# SparkFun_Cypress_USBUART_BOB.net
KiCad netlist of a schematic drawn in EAGLE
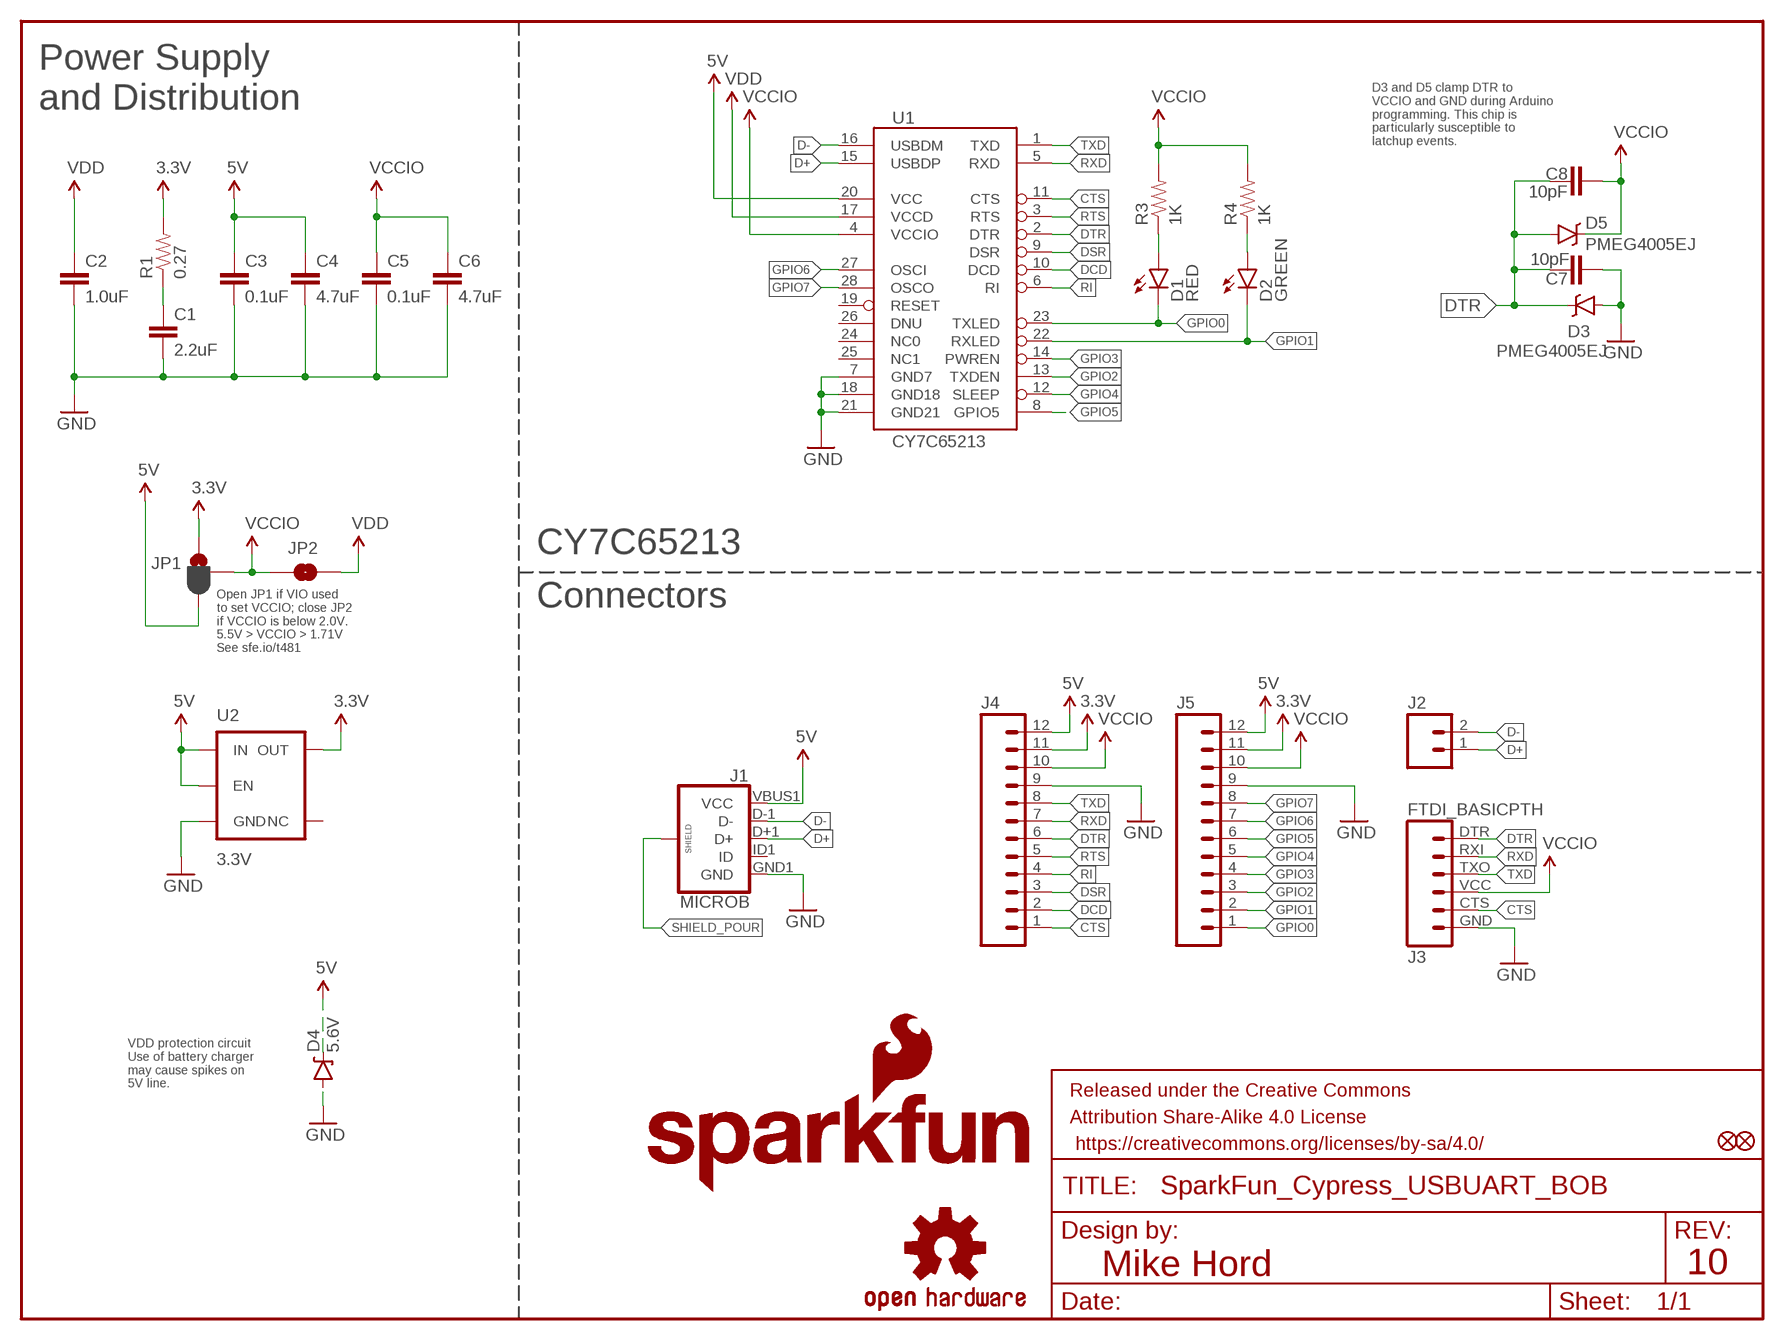
[diagram p0: schematic, sheet 1]

(export (version "E")
  (design (tool "Eeschema 10.0.6"))
  (components
    (comp (ref "C1")
      (value "2.2uF")
      (footprint "eagle-import:0603-CAP")
      (libsource (lib "eagle-import") (part "2.2UF-10V-20%(0603)"))
    )
    (comp (ref "C2")
      (value "1.0uF")
      (footprint "eagle-import:0603-CAP")
      (libsource (lib "eagle-import") (part "1.0UF-16V-10%(0603)"))
    )
    (comp (ref "C3")
      (value "0.1uF")
      (footprint "eagle-import:0603-CAP")
      (libsource (lib "eagle-import") (part "0.1UF-25V-5%(0603)"))
    )
    (comp (ref "C4")
      (value "4.7uF")
      (footprint "eagle-import:1206-CAP")
      (libsource (lib "eagle-import") (part "4.7UF-16V-20%,+80%-(1206)"))
    )
    (comp (ref "C5")
      (value "0.1uF")
      (footprint "eagle-import:0603-CAP")
      (libsource (lib "eagle-import") (part "0.1UF-25V-5%(0603)"))
    )
    (comp (ref "C6")
      (value "4.7uF")
      (footprint "eagle-import:1206-CAP")
      (libsource (lib "eagle-import") (part "4.7UF-16V-20%,+80%-(1206)"))
    )
    (comp (ref "C7")
      (value "10pF")
      (footprint "eagle-import:0603-CAP")
      (libsource (lib "eagle-import") (part "10PF-50V-5%(0603)"))
    )
    (comp (ref "C8")
      (value "10pF")
      (footprint "eagle-import:0603-CAP")
      (libsource (lib "eagle-import") (part "10PF-50V-5%(0603)"))
    )
    (comp (ref "D1")
      (value "RED")
      (footprint "eagle-import:LED-0603")
      (libsource (lib "eagle-import") (part "LED-RED0603"))
    )
    (comp (ref "D2")
      (value "GREEN")
      (footprint "eagle-import:LED-0603")
      (libsource (lib "eagle-import") (part "LED-GREEN0603"))
    )
    (comp (ref "D3")
      (value "PMEG4005EJ")
      (footprint "eagle-import:SOD-323")
      (libsource (lib "eagle-import") (part "DIODE-SCHOTTKY-PMEG4005EJ"))
    )
    (comp (ref "D4")
      (value "5.6V")
      (footprint "eagle-import:SOD-323")
      (libsource (lib "eagle-import") (part "DIODE-ZENER5.6V"))
    )
    (comp (ref "D5")
      (value "PMEG4005EJ")
      (footprint "eagle-import:SOD-323")
      (libsource (lib "eagle-import") (part "DIODE-SCHOTTKY-PMEG4005EJ"))
    )
    (comp (ref "FD1")
      (value "FIDUCIALUFIDUCIAL")
      (footprint "eagle-import:MICRO-FIDUCIAL")
      (libsource (lib "eagle-import") (part "FIDUCIALUFIDUCIAL"))
    )
    (comp (ref "FD2")
      (value "FIDUCIALUFIDUCIAL")
      (footprint "eagle-import:MICRO-FIDUCIAL")
      (libsource (lib "eagle-import") (part "FIDUCIALUFIDUCIAL"))
    )
    (comp (ref "FRAME1")
      (value "FRAME-LETTER")
      (footprint "eagle-import:CREATIVE_COMMONS")
      (libsource (lib "eagle-import") (part "FRAME-LETTER"))
    )
    (comp (ref "J1")
      (value "MICROB")
      (footprint "eagle-import:USB-B-MICRO-SMD_V03")
      (libsource (lib "eagle-import") (part "USB_MICROB_PLUGCONN-11752"))
    )
    (comp (ref "J2")
      (value "M02PTH")
      (footprint "eagle-import:1X02")
      (libsource (lib "eagle-import") (part "M02PTH"))
    )
    (comp (ref "J3")
      (value "FTDI_BASICPTH")
      (footprint "eagle-import:FTDI_BASIC")
      (libsource (lib "eagle-import") (part "FTDI_BASICPTH"))
    )
    (comp (ref "J4")
      (value "M12PTH")
      (footprint "eagle-import:1X12")
      (libsource (lib "eagle-import") (part "M12PTH"))
    )
    (comp (ref "J5")
      (value "M12PTH")
      (footprint "eagle-import:1X12")
      (libsource (lib "eagle-import") (part "M12PTH"))
    )
    (comp (ref "JP1")
      (value "JUMPER-PAD-3-2OF3_NC_BY_PASTE")
      (footprint "eagle-import:PAD-JUMPER-3-2OF3_NC_BY_PASTE_YES_SILK_FULL_BOX")
      (libsource (lib "eagle-import") (part "JUMPER-PAD-3-2OF3_NC_BY_PASTE"))
    )
    (comp (ref "JP2")
      (value "JUMPER-PAD-2-NOYES_SILK")
      (footprint "eagle-import:PAD-JUMPER-2-NO_YES_SILK")
      (libsource (lib "eagle-import") (part "JUMPER-PAD-2-NOYES_SILK"))
    )
    (comp (ref "LOGO1")
      (value "SFE_LOGO_NAME_FLAME.1_INCH")
      (footprint "eagle-import:SFE_LOGO_NAME_FLAME_.1")
      (libsource (lib "eagle-import") (part "SFE_LOGO_NAME_FLAME.1_INCH"))
    )
    (comp (ref "LOGO2")
      (value "OSHW-LOGOS")
      (footprint "eagle-import:OSHW-LOGO-S")
      (libsource (lib "eagle-import") (part "OSHW-LOGOS"))
    )
    (comp (ref "R1")
      (value "0.27")
      (footprint "eagle-import:0603-RES")
      (libsource (lib "eagle-import") (part "0.27OHM-1/10W-1%(0603)"))
    )
    (comp (ref "R3")
      (value "1K")
      (footprint "eagle-import:0603-RES")
      (libsource (lib "eagle-import") (part "1KOHM-1/10W-1%(0603)"))
    )
    (comp (ref "R4")
      (value "1K")
      (footprint "eagle-import:0603-RES")
      (libsource (lib "eagle-import") (part "1KOHM-1/10W-1%(0603)"))
    )
    (comp (ref "U1")
      (value "CY7C65213")
      (footprint "eagle-import:SSOP28DB")
      (libsource (lib "eagle-import") (part "CY7C65213"))
    )
    (comp (ref "U2")
      (value "3.3V")
      (footprint "eagle-import:SOT23-5")
      (libsource (lib "eagle-import") (part "V_REG_AP2112K-3.3V"))
    )
  )
  (nets
    (net (code "1") (name "/NC1") (class "Default")
      (node (ref "U1") (pin "25") (pinfunction "NC1_25") (pintype "power_in"))
    )
    (net (code "2") (name "3.3V") (class "Default")
      (node (ref "J4") (pin "11") (pinfunction "11_11") (pintype "passive"))
      (node (ref "J5") (pin "11") (pinfunction "11_11") (pintype "passive"))
      (node (ref "JP1") (pin "1") (pinfunction "1_1") (pintype "passive"))
      (node (ref "R1") (pin "2") (pinfunction "2_2") (pintype "passive"))
      (node (ref "U2") (pin "5") (pinfunction "OUT_5") (pintype "passive"))
    )
    (net (code "3") (name "5V") (class "Default")
      (node (ref "C3") (pin "1") (pinfunction "1_1") (pintype "passive"))
      (node (ref "C4") (pin "1") (pinfunction "1_1") (pintype "passive"))
      (node (ref "D4") (pin "C") (pinfunction "C_C") (pintype "passive"))
      (node (ref "J1") (pin "VBUS1") (pinfunction "VCC_VBUS1") (pintype "bidirectional"))
      (node (ref "J4") (pin "12") (pinfunction "12_12") (pintype "passive"))
      (node (ref "J5") (pin "12") (pinfunction "12_12") (pintype "passive"))
      (node (ref "JP1") (pin "3") (pinfunction "3_3") (pintype "passive"))
      (node (ref "U1") (pin "20") (pinfunction "VCC_20") (pintype "power_in"))
      (node (ref "U2") (pin "1") (pinfunction "IN_1") (pintype "input"))
      (node (ref "U2") (pin "3") (pinfunction "EN_3") (pintype "input"))
    )
    (net (code "4") (name "CTS") (class "Default")
      (node (ref "J3") (pin "CTS") (pinfunction "5_CTS") (pintype "passive"))
      (node (ref "J4") (pin "1") (pinfunction "1_1") (pintype "passive"))
      (node (ref "U1") (pin "11") (pinfunction "CTS_11") (pintype "input"))
    )
    (net (code "5") (name "D+") (class "Default")
      (node (ref "J1") (pin "D+1") (pinfunction "D+_D+1") (pintype "bidirectional"))
      (node (ref "J2") (pin "1") (pinfunction "1_1") (pintype "passive"))
      (node (ref "U1") (pin "15") (pinfunction "USBDP_15") (pintype "bidirectional"))
    )
    (net (code "6") (name "D-") (class "Default")
      (node (ref "J1") (pin "D-1") (pinfunction "D-_D-1") (pintype "bidirectional"))
      (node (ref "J2") (pin "2") (pinfunction "2_2") (pintype "passive"))
      (node (ref "U1") (pin "16") (pinfunction "USBDM_16") (pintype "bidirectional"))
    )
    (net (code "7") (name "DCD") (class "Default")
      (node (ref "J4") (pin "2") (pinfunction "2_2") (pintype "passive"))
      (node (ref "U1") (pin "10") (pinfunction "DCD_10") (pintype "input"))
    )
    (net (code "8") (name "DSR") (class "Default")
      (node (ref "J4") (pin "3") (pinfunction "3_3") (pintype "passive"))
      (node (ref "U1") (pin "9") (pinfunction "DSR_9") (pintype "input"))
    )
    (net (code "9") (name "DTR") (class "Default")
      (node (ref "C7") (pin "1") (pinfunction "1_1") (pintype "passive"))
      (node (ref "C8") (pin "1") (pinfunction "1_1") (pintype "passive"))
      (node (ref "D3") (pin "C") (pinfunction "C_C") (pintype "passive"))
      (node (ref "D5") (pin "A") (pinfunction "A_A") (pintype "passive"))
      (node (ref "J3") (pin "DTR") (pinfunction "1_DTR") (pintype "passive"))
      (node (ref "J4") (pin "6") (pinfunction "6_6") (pintype "passive"))
      (node (ref "U1") (pin "2") (pinfunction "DTR_2") (pintype "output"))
    )
    (net (code "10") (name "GND") (class "Default")
      (node (ref "C1") (pin "2") (pinfunction "2_2") (pintype "passive"))
      (node (ref "C2") (pin "2") (pinfunction "2_2") (pintype "passive"))
      (node (ref "C3") (pin "2") (pinfunction "2_2") (pintype "passive"))
      (node (ref "C4") (pin "2") (pinfunction "2_2") (pintype "passive"))
      (node (ref "C5") (pin "2") (pinfunction "2_2") (pintype "passive"))
      (node (ref "C6") (pin "2") (pinfunction "2_2") (pintype "passive"))
      (node (ref "C7") (pin "2") (pinfunction "2_2") (pintype "passive"))
      (node (ref "D3") (pin "A") (pinfunction "A_A") (pintype "passive"))
      (node (ref "D4") (pin "A") (pinfunction "A_A") (pintype "passive"))
      (node (ref "J1") (pin "GND1") (pinfunction "GND_GND1") (pintype "bidirectional"))
      (node (ref "J3") (pin "GND") (pinfunction "6_GND") (pintype "passive"))
      (node (ref "J4") (pin "9") (pinfunction "9_9") (pintype "passive"))
      (node (ref "J5") (pin "9") (pinfunction "9_9") (pintype "passive"))
      (node (ref "U1") (pin "18") (pinfunction "GND18_18") (pintype "power_in"))
      (node (ref "U1") (pin "21") (pinfunction "GND21_21") (pintype "power_in"))
      (node (ref "U1") (pin "7") (pinfunction "GND7_7") (pintype "power_in"))
      (node (ref "U2") (pin "2") (pinfunction "GND_2") (pintype "input"))
    )
    (net (code "11") (name "GPIO0") (class "Default")
      (node (ref "D1") (pin "C") (pinfunction "C_C") (pintype "passive"))
      (node (ref "J5") (pin "1") (pinfunction "1_1") (pintype "passive"))
      (node (ref "U1") (pin "23") (pinfunction "TXLED_23") (pintype "input"))
    )
    (net (code "12") (name "GPIO1") (class "Default")
      (node (ref "D2") (pin "C") (pinfunction "C_C") (pintype "passive"))
      (node (ref "J5") (pin "2") (pinfunction "2_2") (pintype "passive"))
      (node (ref "U1") (pin "22") (pinfunction "RXLED_22") (pintype "input"))
    )
    (net (code "13") (name "GPIO2") (class "Default")
      (node (ref "J5") (pin "3") (pinfunction "3_3") (pintype "passive"))
      (node (ref "U1") (pin "13") (pinfunction "TXDEN_13") (pintype "input"))
    )
    (net (code "14") (name "GPIO3") (class "Default")
      (node (ref "J5") (pin "4") (pinfunction "4_4") (pintype "passive"))
      (node (ref "U1") (pin "14") (pinfunction "PWREN_14") (pintype "input"))
    )
    (net (code "15") (name "GPIO4") (class "Default")
      (node (ref "J5") (pin "5") (pinfunction "5_5") (pintype "passive"))
      (node (ref "U1") (pin "12") (pinfunction "SLEEP_12") (pintype "input"))
    )
    (net (code "16") (name "GPIO5") (class "Default")
      (node (ref "J5") (pin "6") (pinfunction "6_6") (pintype "passive"))
      (node (ref "U1") (pin "8") (pinfunction "GPIO5_8") (pintype "input"))
    )
    (net (code "17") (name "GPIO6") (class "Default")
      (node (ref "J5") (pin "7") (pinfunction "7_7") (pintype "passive"))
      (node (ref "U1") (pin "27") (pinfunction "OSCI_27") (pintype "input"))
    )
    (net (code "18") (name "GPIO7") (class "Default")
      (node (ref "J5") (pin "8") (pinfunction "8_8") (pintype "passive"))
      (node (ref "U1") (pin "28") (pinfunction "OSCO_28") (pintype "output"))
    )
    (net (code "19") (name "Net-(C1-Pad1)") (class "Default")
      (node (ref "C1") (pin "1") (pinfunction "1_1") (pintype "passive"))
      (node (ref "R1") (pin "1") (pinfunction "1_1") (pintype "passive"))
    )
    (net (code "20") (name "Net-(D1-PadA)") (class "Default")
      (node (ref "D1") (pin "A") (pinfunction "A_A") (pintype "passive"))
      (node (ref "R3") (pin "1") (pinfunction "1_1") (pintype "passive"))
    )
    (net (code "21") (name "Net-(D2-PadA)") (class "Default")
      (node (ref "D2") (pin "A") (pinfunction "A_A") (pintype "passive"))
      (node (ref "R4") (pin "1") (pinfunction "1_1") (pintype "passive"))
    )
    (net (code "22") (name "RI") (class "Default")
      (node (ref "J4") (pin "4") (pinfunction "4_4") (pintype "passive"))
      (node (ref "U1") (pin "6") (pinfunction "RI_6") (pintype "input"))
    )
    (net (code "23") (name "RTS") (class "Default")
      (node (ref "J4") (pin "5") (pinfunction "5_5") (pintype "passive"))
      (node (ref "U1") (pin "3") (pinfunction "RTS_3") (pintype "output"))
    )
    (net (code "24") (name "RXD") (class "Default")
      (node (ref "J3") (pin "RXI") (pinfunction "2_RXI") (pintype "passive"))
      (node (ref "J4") (pin "7") (pinfunction "7_7") (pintype "passive"))
      (node (ref "U1") (pin "5") (pinfunction "RXD_5") (pintype "input"))
    )
    (net (code "25") (name "SHIELD_POUR") (class "Default")
      (node (ref "J1") (pin "SHIELD1") (pinfunction "SHIELD_SHIELD1") (pintype "bidirectional"))
      (node (ref "J1") (pin "SHIELD2") (pinfunction "SHIELD_SHIELD2") (pintype "bidirectional"))
      (node (ref "J1") (pin "SHIELD3") (pinfunction "SHIELD_SHIELD3") (pintype "bidirectional"))
    )
    (net (code "26") (name "TXD") (class "Default")
      (node (ref "J3") (pin "TXO") (pinfunction "3_TXO") (pintype "passive"))
      (node (ref "J4") (pin "8") (pinfunction "8_8") (pintype "passive"))
      (node (ref "U1") (pin "1") (pinfunction "TXD_1") (pintype "output"))
    )
    (net (code "27") (name "VCCIO") (class "Default")
      (node (ref "C5") (pin "1") (pinfunction "1_1") (pintype "passive"))
      (node (ref "C6") (pin "1") (pinfunction "1_1") (pintype "passive"))
      (node (ref "C8") (pin "2") (pinfunction "2_2") (pintype "passive"))
      (node (ref "D5") (pin "C") (pinfunction "C_C") (pintype "passive"))
      (node (ref "J3") (pin "VCC") (pinfunction "4_VCC") (pintype "passive"))
      (node (ref "J4") (pin "10") (pinfunction "10_10") (pintype "passive"))
      (node (ref "J5") (pin "10") (pinfunction "10_10") (pintype "passive"))
      (node (ref "JP1") (pin "2") (pinfunction "2_2") (pintype "passive"))
      (node (ref "JP2") (pin "1") (pinfunction "1_1") (pintype "passive"))
      (node (ref "R3") (pin "2") (pinfunction "2_2") (pintype "passive"))
      (node (ref "R4") (pin "2") (pinfunction "2_2") (pintype "passive"))
      (node (ref "U1") (pin "4") (pinfunction "VCCIO_4") (pintype "power_in"))
    )
    (net (code "28") (name "VDD") (class "Default")
      (node (ref "C2") (pin "1") (pinfunction "1_1") (pintype "passive"))
      (node (ref "JP2") (pin "2") (pinfunction "2_2") (pintype "passive"))
      (node (ref "U1") (pin "17") (pinfunction "VCCD_17") (pintype "output"))
    )
    (net (code "29") (name "unconnected-(J1-ID-PadID1)") (class "Default")
      (node (ref "J1") (pin "ID1") (pinfunction "ID_ID1") (pintype "bidirectional"))
    )
    (net (code "30") (name "unconnected-(U1-DNU-Pad26)") (class "Default")
      (node (ref "U1") (pin "26") (pinfunction "DNU_26") (pintype "input"))
    )
    (net (code "31") (name "unconnected-(U1-NC0-Pad24)") (class "Default")
      (node (ref "U1") (pin "24") (pinfunction "NC0_24") (pintype "input"))
    )
    (net (code "32") (name "unconnected-(U1-RESET-Pad19)") (class "Default")
      (node (ref "U1") (pin "19") (pinfunction "RESET_19") (pintype "input"))
    )
    (net (code "33") (name "unconnected-(U2-NC-Pad4)") (class "Default")
      (node (ref "U2") (pin "4") (pinfunction "NC_4") (pintype "input"))
    )
  )
)
